# R302J.net
KiCad netlist of a schematic drawn in EAGLE
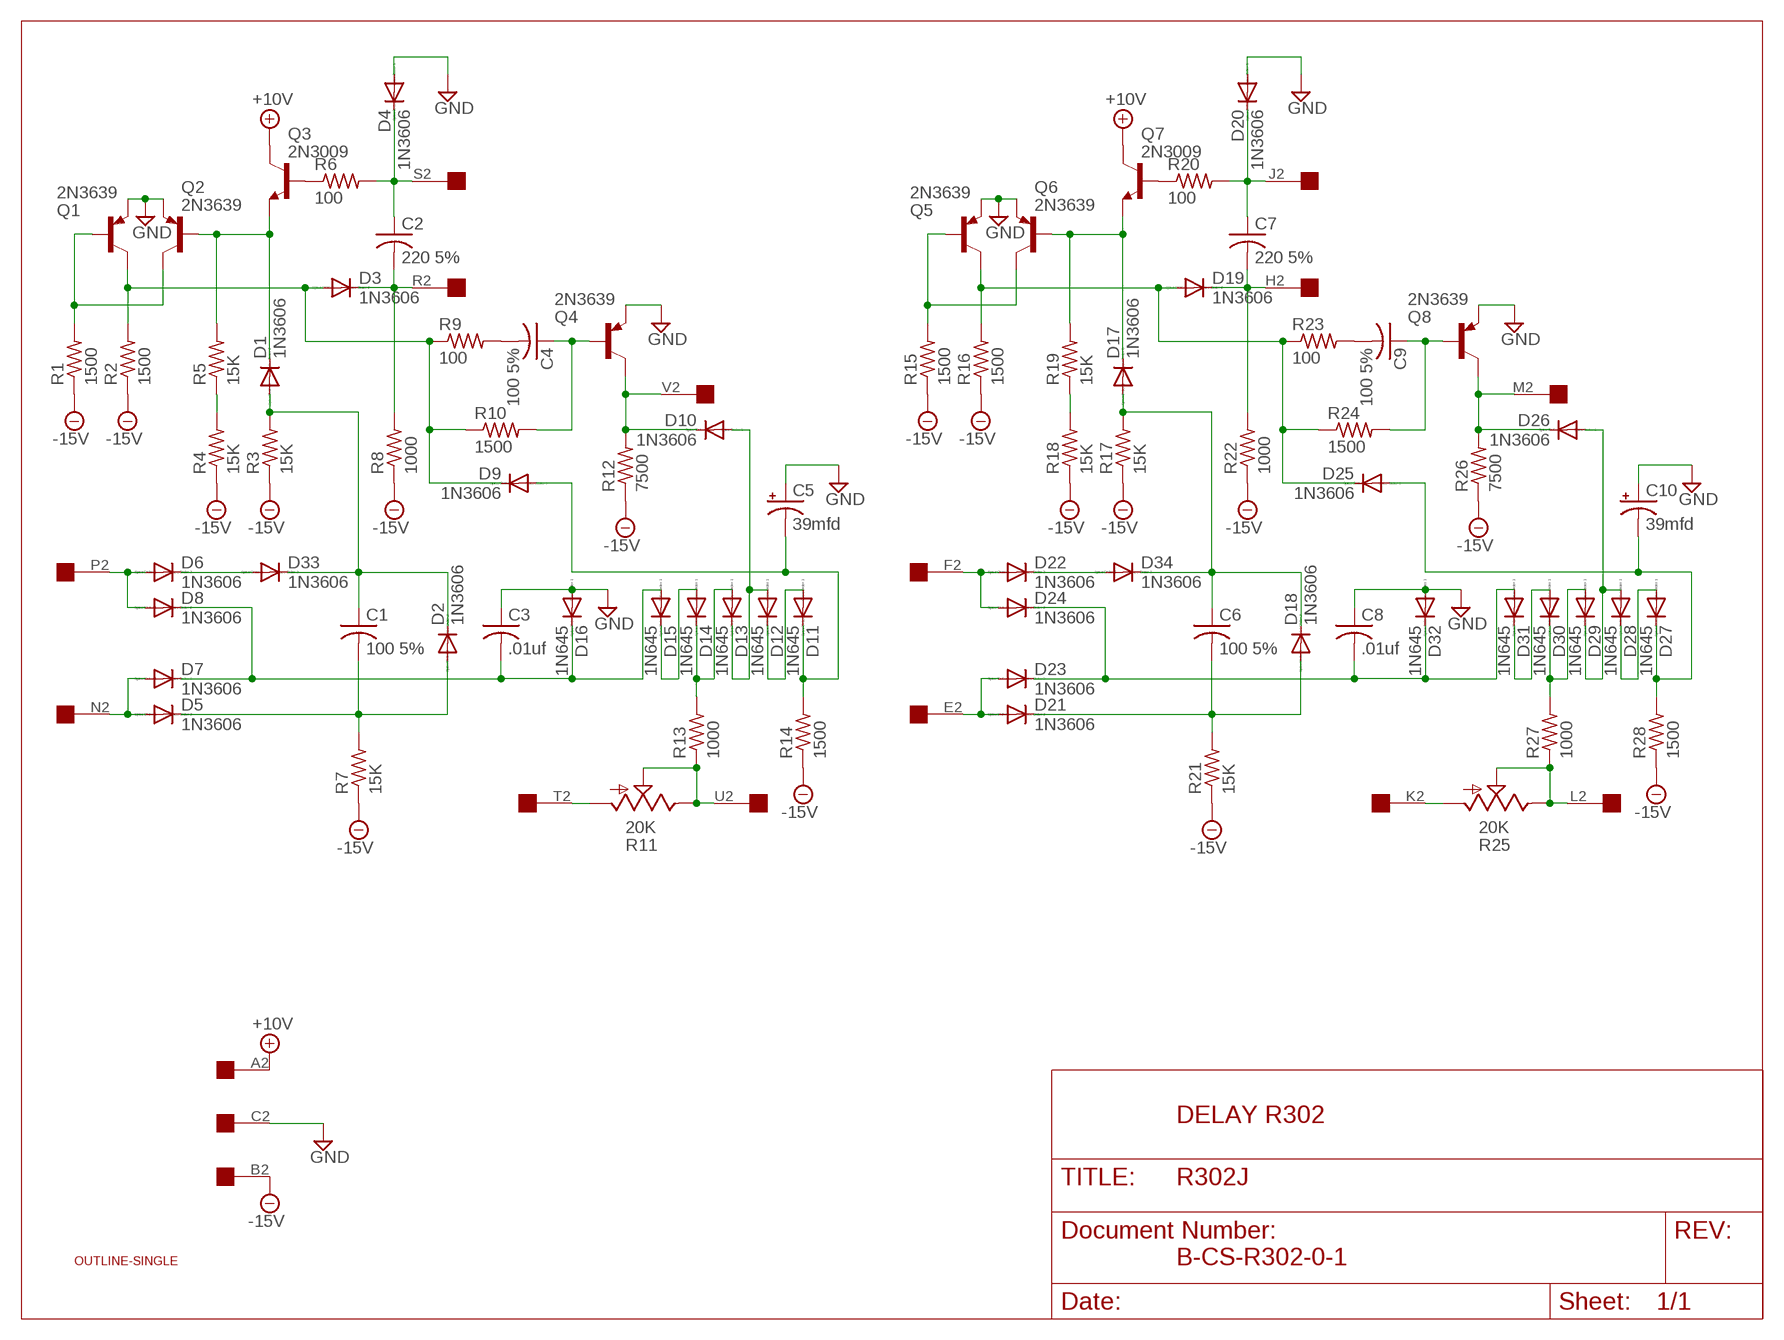
[diagram p0: schematic, sheet 1]

(export (version "E")
  (design (tool "Eeschema 10.0.6"))
  (components
    (comp (ref "C1")
      (value "100 5%")
      (footprint "eagle-import:C050-025X075")
      (libsource (lib "eagle-import") (part "C-US050-025X075"))
    )
    (comp (ref "C2")
      (value "220 5%")
      (footprint "eagle-import:C050-025X075")
      (libsource (lib "eagle-import") (part "C-US050-025X075"))
    )
    (comp (ref "C3")
      (value ".01uf")
      (footprint "eagle-import:C050-025X075")
      (libsource (lib "eagle-import") (part "C-US050-025X075"))
    )
    (comp (ref "C4")
      (value "100 5%")
      (footprint "eagle-import:C050-025X075")
      (libsource (lib "eagle-import") (part "C-US050-025X075"))
    )
    (comp (ref "C5")
      (value "39mfd")
      (footprint "eagle-import:E15-5")
      (libsource (lib "eagle-import") (part "CPOL-USE15-5AXIAL"))
    )
    (comp (ref "C6")
      (value "100 5%")
      (footprint "eagle-import:C050-025X075")
      (libsource (lib "eagle-import") (part "C-US050-025X075"))
    )
    (comp (ref "C7")
      (value "220 5%")
      (footprint "eagle-import:C050-025X075")
      (libsource (lib "eagle-import") (part "C-US050-025X075"))
    )
    (comp (ref "C8")
      (value ".01uf")
      (footprint "eagle-import:C050-025X075")
      (libsource (lib "eagle-import") (part "C-US050-025X075"))
    )
    (comp (ref "C9")
      (value "100 5%")
      (footprint "eagle-import:C050-025X075")
      (libsource (lib "eagle-import") (part "C-US050-025X075"))
    )
    (comp (ref "C10")
      (value "39mfd")
      (footprint "eagle-import:E15-5")
      (libsource (lib "eagle-import") (part "CPOL-USE15-5AXIAL"))
    )
    (comp (ref "D1")
      (value "1N3606")
      (footprint "eagle-import:DO35-10")
      (libsource (lib "eagle-import") (part "1N4148DO35-10"))
    )
    (comp (ref "D2")
      (value "1N3606")
      (footprint "eagle-import:DO35-10")
      (libsource (lib "eagle-import") (part "1N4148DO35-10"))
    )
    (comp (ref "D3")
      (value "1N3606")
      (footprint "eagle-import:DO35-10")
      (libsource (lib "eagle-import") (part "1N4148DO35-10"))
    )
    (comp (ref "D4")
      (value "1N3606")
      (footprint "eagle-import:DO35-10")
      (libsource (lib "eagle-import") (part "1N4148DO35-10"))
    )
    (comp (ref "D5")
      (value "1N3606")
      (footprint "eagle-import:DO35-10")
      (libsource (lib "eagle-import") (part "1N4148DO35-10"))
    )
    (comp (ref "D6")
      (value "1N3606")
      (footprint "eagle-import:DO35-10")
      (libsource (lib "eagle-import") (part "1N4148DO35-10"))
    )
    (comp (ref "D7")
      (value "1N3606")
      (footprint "eagle-import:DO35-10")
      (libsource (lib "eagle-import") (part "1N4148DO35-10"))
    )
    (comp (ref "D8")
      (value "1N3606")
      (footprint "eagle-import:DO35-10")
      (libsource (lib "eagle-import") (part "1N4148DO35-10"))
    )
    (comp (ref "D9")
      (value "1N3606")
      (footprint "eagle-import:DO35-10")
      (libsource (lib "eagle-import") (part "1N4148DO35-10"))
    )
    (comp (ref "D10")
      (value "1N3606")
      (footprint "eagle-import:DO35-10")
      (libsource (lib "eagle-import") (part "1N4148DO35-10"))
    )
    (comp (ref "D11")
      (value "1N645")
      (footprint "eagle-import:DO35-10")
      (libsource (lib "eagle-import") (part "1N4148DO35-10"))
    )
    (comp (ref "D12")
      (value "1N645")
      (footprint "eagle-import:DO35-10")
      (libsource (lib "eagle-import") (part "1N4148DO35-10"))
    )
    (comp (ref "D13")
      (value "1N645")
      (footprint "eagle-import:DO35-10")
      (libsource (lib "eagle-import") (part "1N4148DO35-10"))
    )
    (comp (ref "D14")
      (value "1N645")
      (footprint "eagle-import:DO35-10")
      (libsource (lib "eagle-import") (part "1N4148DO35-10"))
    )
    (comp (ref "D15")
      (value "1N645")
      (footprint "eagle-import:DO35-10")
      (libsource (lib "eagle-import") (part "1N4148DO35-10"))
    )
    (comp (ref "D16")
      (value "1N645")
      (footprint "eagle-import:DO35-10")
      (libsource (lib "eagle-import") (part "1N4148DO35-10"))
    )
    (comp (ref "D17")
      (value "1N3606")
      (footprint "eagle-import:DO35-10")
      (libsource (lib "eagle-import") (part "1N4148DO35-10"))
    )
    (comp (ref "D18")
      (value "1N3606")
      (footprint "eagle-import:DO35-10")
      (libsource (lib "eagle-import") (part "1N4148DO35-10"))
    )
    (comp (ref "D19")
      (value "1N3606")
      (footprint "eagle-import:DO35-10")
      (libsource (lib "eagle-import") (part "1N4148DO35-10"))
    )
    (comp (ref "D20")
      (value "1N3606")
      (footprint "eagle-import:DO35-10")
      (libsource (lib "eagle-import") (part "1N4148DO35-10"))
    )
    (comp (ref "D21")
      (value "1N3606")
      (footprint "eagle-import:DO35-10")
      (libsource (lib "eagle-import") (part "1N4148DO35-10"))
    )
    (comp (ref "D22")
      (value "1N3606")
      (footprint "eagle-import:DO35-10")
      (libsource (lib "eagle-import") (part "1N4148DO35-10"))
    )
    (comp (ref "D23")
      (value "1N3606")
      (footprint "eagle-import:DO35-10")
      (libsource (lib "eagle-import") (part "1N4148DO35-10"))
    )
    (comp (ref "D24")
      (value "1N3606")
      (footprint "eagle-import:DO35-10")
      (libsource (lib "eagle-import") (part "1N4148DO35-10"))
    )
    (comp (ref "D25")
      (value "1N3606")
      (footprint "eagle-import:DO35-10")
      (libsource (lib "eagle-import") (part "1N4148DO35-10"))
    )
    (comp (ref "D26")
      (value "1N3606")
      (footprint "eagle-import:DO35-10")
      (libsource (lib "eagle-import") (part "1N4148DO35-10"))
    )
    (comp (ref "D27")
      (value "1N645")
      (footprint "eagle-import:DO35-10")
      (libsource (lib "eagle-import") (part "1N4148DO35-10"))
    )
    (comp (ref "D28")
      (value "1N645")
      (footprint "eagle-import:DO35-10")
      (libsource (lib "eagle-import") (part "1N4148DO35-10"))
    )
    (comp (ref "D29")
      (value "1N645")
      (footprint "eagle-import:DO35-10")
      (libsource (lib "eagle-import") (part "1N4148DO35-10"))
    )
    (comp (ref "D30")
      (value "1N645")
      (footprint "eagle-import:DO35-10")
      (libsource (lib "eagle-import") (part "1N4148DO35-10"))
    )
    (comp (ref "D31")
      (value "1N645")
      (footprint "eagle-import:DO35-10")
      (libsource (lib "eagle-import") (part "1N4148DO35-10"))
    )
    (comp (ref "D32")
      (value "1N645")
      (footprint "eagle-import:DO35-10")
      (libsource (lib "eagle-import") (part "1N4148DO35-10"))
    )
    (comp (ref "D33")
      (value "1N3606")
      (footprint "eagle-import:DO35-10")
      (libsource (lib "eagle-import") (part "1N4148DO35-10"))
    )
    (comp (ref "D34")
      (value "1N3606")
      (footprint "eagle-import:DO35-10")
      (libsource (lib "eagle-import") (part "1N4148DO35-10"))
    )
    (comp (ref "Q1")
      (value "2N3639")
      (footprint "eagle-import:TO39")
      (libsource (lib "eagle-import") (part "2N3637"))
    )
    (comp (ref "Q2")
      (value "2N3639")
      (footprint "eagle-import:TO39")
      (libsource (lib "eagle-import") (part "2N3637"))
    )
    (comp (ref "Q3")
      (value "2N3009")
      (footprint "eagle-import:TO39")
      (libsource (lib "eagle-import") (part "-NPN-TO39-EBC2N3019"))
    )
    (comp (ref "Q4")
      (value "2N3639")
      (footprint "eagle-import:TO39")
      (libsource (lib "eagle-import") (part "2N3637"))
    )
    (comp (ref "Q5")
      (value "2N3639")
      (footprint "eagle-import:TO39")
      (libsource (lib "eagle-import") (part "2N3637"))
    )
    (comp (ref "Q6")
      (value "2N3639")
      (footprint "eagle-import:TO39")
      (libsource (lib "eagle-import") (part "2N3637"))
    )
    (comp (ref "Q7")
      (value "2N3009")
      (footprint "eagle-import:TO39")
      (libsource (lib "eagle-import") (part "-NPN-TO39-EBC2N3019"))
    )
    (comp (ref "Q8")
      (value "2N3639")
      (footprint "eagle-import:TO39")
      (libsource (lib "eagle-import") (part "2N3637"))
    )
    (comp (ref "R1")
      (value "1500")
      (footprint "eagle-import:0207_10")
      (libsource (lib "eagle-import") (part "R-US_0207/10"))
    )
    (comp (ref "R2")
      (value "1500")
      (footprint "eagle-import:0207_10")
      (libsource (lib "eagle-import") (part "R-US_0207/10"))
    )
    (comp (ref "R3")
      (value "15K")
      (footprint "eagle-import:0207_10")
      (libsource (lib "eagle-import") (part "R-US_0207/10"))
    )
    (comp (ref "R4")
      (value "15K")
      (footprint "eagle-import:0207_10")
      (libsource (lib "eagle-import") (part "R-US_0207/10"))
    )
    (comp (ref "R5")
      (value "15K")
      (footprint "eagle-import:0207_10")
      (libsource (lib "eagle-import") (part "R-US_0207/10"))
    )
    (comp (ref "R6")
      (value "100")
      (footprint "eagle-import:0207_10")
      (libsource (lib "eagle-import") (part "R-US_0207/10"))
    )
    (comp (ref "R7")
      (value "15K")
      (footprint "eagle-import:0207_10")
      (libsource (lib "eagle-import") (part "R-US_0207/10"))
    )
    (comp (ref "R8")
      (value "1000")
      (footprint "eagle-import:0207_10")
      (libsource (lib "eagle-import") (part "R-US_0207/10"))
    )
    (comp (ref "R9")
      (value "100")
      (footprint "eagle-import:0207_10")
      (libsource (lib "eagle-import") (part "R-US_0207/10"))
    )
    (comp (ref "R10")
      (value "1500")
      (footprint "eagle-import:0207_10")
      (libsource (lib "eagle-import") (part "R-US_0207/10"))
    )
    (comp (ref "R11")
      (value "20K")
      (footprint "eagle-import:SP19L")
      (libsource (lib "eagle-import") (part "TRIM_US-S43P"))
    )
    (comp (ref "R12")
      (value "7500")
      (footprint "eagle-import:0207_10")
      (libsource (lib "eagle-import") (part "R-US_0207/10"))
    )
    (comp (ref "R13")
      (value "1000")
      (footprint "eagle-import:0207_10")
      (libsource (lib "eagle-import") (part "R-US_0207/10"))
    )
    (comp (ref "R14")
      (value "1500")
      (footprint "eagle-import:0207_10")
      (libsource (lib "eagle-import") (part "R-US_0207/10"))
    )
    (comp (ref "R15")
      (value "1500")
      (footprint "eagle-import:0207_10")
      (libsource (lib "eagle-import") (part "R-US_0207/10"))
    )
    (comp (ref "R16")
      (value "1500")
      (footprint "eagle-import:0207_10")
      (libsource (lib "eagle-import") (part "R-US_0207/10"))
    )
    (comp (ref "R17")
      (value "15K")
      (footprint "eagle-import:0207_10")
      (libsource (lib "eagle-import") (part "R-US_0207/10"))
    )
    (comp (ref "R18")
      (value "15K")
      (footprint "eagle-import:0207_10")
      (libsource (lib "eagle-import") (part "R-US_0207/10"))
    )
    (comp (ref "R19")
      (value "15K")
      (footprint "eagle-import:0207_10")
      (libsource (lib "eagle-import") (part "R-US_0207/10"))
    )
    (comp (ref "R20")
      (value "100")
      (footprint "eagle-import:0207_10")
      (libsource (lib "eagle-import") (part "R-US_0207/10"))
    )
    (comp (ref "R21")
      (value "15K")
      (footprint "eagle-import:0207_10")
      (libsource (lib "eagle-import") (part "R-US_0207/10"))
    )
    (comp (ref "R22")
      (value "1000")
      (footprint "eagle-import:0207_10")
      (libsource (lib "eagle-import") (part "R-US_0207/10"))
    )
    (comp (ref "R23")
      (value "100")
      (footprint "eagle-import:0207_10")
      (libsource (lib "eagle-import") (part "R-US_0207/10"))
    )
    (comp (ref "R24")
      (value "1500")
      (footprint "eagle-import:0207_10")
      (libsource (lib "eagle-import") (part "R-US_0207/10"))
    )
    (comp (ref "R25")
      (value "20K")
      (footprint "eagle-import:SP19L")
      (libsource (lib "eagle-import") (part "TRIM_US-S43P"))
    )
    (comp (ref "R26")
      (value "7500")
      (footprint "eagle-import:0207_10")
      (libsource (lib "eagle-import") (part "R-US_0207/10"))
    )
    (comp (ref "R27")
      (value "1000")
      (footprint "eagle-import:0207_10")
      (libsource (lib "eagle-import") (part "R-US_0207/10"))
    )
    (comp (ref "R28")
      (value "1500")
      (footprint "eagle-import:0207_10")
      (libsource (lib "eagle-import") (part "R-US_0207/10"))
    )
    (comp (ref "U$1")
      (value "OUTLINE-SINGLE")
      (footprint "eagle-import:SINGLE")
      (libsource (lib "eagle-import") (part "OUTLINE-SINGLE"))
    )
    (comp (ref "U$2")
      (value "EDGE-1")
      (footprint "eagle-import:EDGE-CON1")
      (libsource (lib "eagle-import") (part "EDGE-1"))
    )
  )
  (nets
    (net (code "1") (name "+10V") (class "Default")
      (node (ref "Q3") (pin "3") (pinfunction "C_3") (pintype "passive"))
      (node (ref "Q7") (pin "3") (pinfunction "C_3") (pintype "passive"))
      (node (ref "U$2") (pin "A2") (pinfunction "1_A2") (pintype "bidirectional"))
    )
    (net (code "2") (name "-15V") (class "Default")
      (node (ref "R1") (pin "1") (pinfunction "1_1") (pintype "passive"))
      (node (ref "R12") (pin "1") (pinfunction "1_1") (pintype "passive"))
      (node (ref "R14") (pin "1") (pinfunction "1_1") (pintype "passive"))
      (node (ref "R15") (pin "1") (pinfunction "1_1") (pintype "passive"))
      (node (ref "R16") (pin "1") (pinfunction "1_1") (pintype "passive"))
      (node (ref "R17") (pin "1") (pinfunction "1_1") (pintype "passive"))
      (node (ref "R18") (pin "1") (pinfunction "1_1") (pintype "passive"))
      (node (ref "R2") (pin "1") (pinfunction "1_1") (pintype "passive"))
      (node (ref "R21") (pin "1") (pinfunction "1_1") (pintype "passive"))
      (node (ref "R22") (pin "1") (pinfunction "1_1") (pintype "passive"))
      (node (ref "R26") (pin "1") (pinfunction "1_1") (pintype "passive"))
      (node (ref "R28") (pin "1") (pinfunction "1_1") (pintype "passive"))
      (node (ref "R3") (pin "1") (pinfunction "1_1") (pintype "passive"))
      (node (ref "R4") (pin "1") (pinfunction "1_1") (pintype "passive"))
      (node (ref "R7") (pin "1") (pinfunction "1_1") (pintype "passive"))
      (node (ref "R8") (pin "1") (pinfunction "1_1") (pintype "passive"))
      (node (ref "U$2") (pin "B2") (pinfunction "1_B2") (pintype "bidirectional"))
    )
    (net (code "3") (name "GND") (class "Default")
      (node (ref "C10") (pin "+") (pinfunction "+_+") (pintype "passive"))
      (node (ref "C3") (pin "1") (pinfunction "1_1") (pintype "passive"))
      (node (ref "C5") (pin "+") (pinfunction "+_+") (pintype "passive"))
      (node (ref "C8") (pin "1") (pinfunction "1_1") (pintype "passive"))
      (node (ref "D16") (pin "A") (pinfunction "A_A") (pintype "passive"))
      (node (ref "D20") (pin "A") (pinfunction "A_A") (pintype "passive"))
      (node (ref "D32") (pin "A") (pinfunction "A_A") (pintype "passive"))
      (node (ref "D4") (pin "A") (pinfunction "A_A") (pintype "passive"))
      (node (ref "Q1") (pin "1") (pinfunction "E_1") (pintype "passive"))
      (node (ref "Q2") (pin "1") (pinfunction "E_1") (pintype "passive"))
      (node (ref "Q4") (pin "1") (pinfunction "E_1") (pintype "passive"))
      (node (ref "Q5") (pin "1") (pinfunction "E_1") (pintype "passive"))
      (node (ref "Q6") (pin "1") (pinfunction "E_1") (pintype "passive"))
      (node (ref "Q8") (pin "1") (pinfunction "E_1") (pintype "passive"))
      (node (ref "U$2") (pin "C2") (pinfunction "1_C2") (pintype "bidirectional"))
    )
    (net (code "4") (name "Net-(C1-Pad1)") (class "Default")
      (node (ref "C1") (pin "1") (pinfunction "1_1") (pintype "passive"))
      (node (ref "D1") (pin "A") (pinfunction "A_A") (pintype "passive"))
      (node (ref "D2") (pin "C") (pinfunction "C_C") (pintype "passive"))
      (node (ref "D33") (pin "C") (pinfunction "C_C") (pintype "passive"))
      (node (ref "R3") (pin "2") (pinfunction "2_2") (pintype "passive"))
    )
    (net (code "5") (name "Net-(C1-Pad2)") (class "Default")
      (node (ref "C1") (pin "2") (pinfunction "2_2") (pintype "passive"))
      (node (ref "D2") (pin "A") (pinfunction "A_A") (pintype "passive"))
      (node (ref "D5") (pin "C") (pinfunction "C_C") (pintype "passive"))
      (node (ref "R7") (pin "2") (pinfunction "2_2") (pintype "passive"))
    )
    (net (code "6") (name "Net-(C3-Pad2)") (class "Default")
      (node (ref "C3") (pin "2") (pinfunction "2_2") (pintype "passive"))
      (node (ref "D15") (pin "A") (pinfunction "A_A") (pintype "passive"))
      (node (ref "D16") (pin "C") (pinfunction "C_C") (pintype "passive"))
      (node (ref "D7") (pin "C") (pinfunction "C_C") (pintype "passive"))
      (node (ref "D8") (pin "C") (pinfunction "C_C") (pintype "passive"))
    )
    (net (code "7") (name "Net-(C4-Pad2)") (class "Default")
      (node (ref "C4") (pin "2") (pinfunction "2_2") (pintype "passive"))
      (node (ref "R9") (pin "2") (pinfunction "2_2") (pintype "passive"))
    )
    (net (code "8") (name "Net-(C5-Pad-)") (class "Default")
      (node (ref "C5") (pin "-") (pinfunction "-_-") (pintype "passive"))
      (node (ref "D11") (pin "C") (pinfunction "C_C") (pintype "passive"))
      (node (ref "D9") (pin "A") (pinfunction "A_A") (pintype "passive"))
      (node (ref "R14") (pin "2") (pinfunction "2_2") (pintype "passive"))
    )
    (net (code "9") (name "Net-(C6-Pad1)") (class "Default")
      (node (ref "C6") (pin "1") (pinfunction "1_1") (pintype "passive"))
      (node (ref "D17") (pin "A") (pinfunction "A_A") (pintype "passive"))
      (node (ref "D18") (pin "C") (pinfunction "C_C") (pintype "passive"))
      (node (ref "D34") (pin "C") (pinfunction "C_C") (pintype "passive"))
      (node (ref "R17") (pin "2") (pinfunction "2_2") (pintype "passive"))
    )
    (net (code "10") (name "Net-(C6-Pad2)") (class "Default")
      (node (ref "C6") (pin "2") (pinfunction "2_2") (pintype "passive"))
      (node (ref "D18") (pin "A") (pinfunction "A_A") (pintype "passive"))
      (node (ref "D21") (pin "C") (pinfunction "C_C") (pintype "passive"))
      (node (ref "R21") (pin "2") (pinfunction "2_2") (pintype "passive"))
    )
    (net (code "11") (name "Net-(C8-Pad2)") (class "Default")
      (node (ref "C8") (pin "2") (pinfunction "2_2") (pintype "passive"))
      (node (ref "D23") (pin "C") (pinfunction "C_C") (pintype "passive"))
      (node (ref "D24") (pin "C") (pinfunction "C_C") (pintype "passive"))
      (node (ref "D31") (pin "A") (pinfunction "A_A") (pintype "passive"))
      (node (ref "D32") (pin "C") (pinfunction "C_C") (pintype "passive"))
    )
    (net (code "12") (name "Net-(C9-Pad2)") (class "Default")
      (node (ref "C9") (pin "2") (pinfunction "2_2") (pintype "passive"))
      (node (ref "R23") (pin "2") (pinfunction "2_2") (pintype "passive"))
    )
    (net (code "13") (name "Net-(C10-Pad-)") (class "Default")
      (node (ref "C10") (pin "-") (pinfunction "-_-") (pintype "passive"))
      (node (ref "D25") (pin "A") (pinfunction "A_A") (pintype "passive"))
      (node (ref "D27") (pin "C") (pinfunction "C_C") (pintype "passive"))
      (node (ref "R28") (pin "2") (pinfunction "2_2") (pintype "passive"))
    )
    (net (code "14") (name "Net-(D10-PadA)") (class "Default")
      (node (ref "D10") (pin "A") (pinfunction "A_A") (pintype "passive"))
      (node (ref "D12") (pin "A") (pinfunction "A_A") (pintype "passive"))
      (node (ref "D13") (pin "C") (pinfunction "C_C") (pintype "passive"))
    )
    (net (code "15") (name "Net-(D11-PadA)") (class "Default")
      (node (ref "D11") (pin "A") (pinfunction "A_A") (pintype "passive"))
      (node (ref "D12") (pin "C") (pinfunction "C_C") (pintype "passive"))
    )
    (net (code "16") (name "Net-(D13-PadA)") (class "Default")
      (node (ref "D13") (pin "A") (pinfunction "A_A") (pintype "passive"))
      (node (ref "D14") (pin "C") (pinfunction "C_C") (pintype "passive"))
      (node (ref "R13") (pin "2") (pinfunction "2_2") (pintype "passive"))
    )
    (net (code "17") (name "Net-(D14-PadA)") (class "Default")
      (node (ref "D14") (pin "A") (pinfunction "A_A") (pintype "passive"))
      (node (ref "D15") (pin "C") (pinfunction "C_C") (pintype "passive"))
    )
    (net (code "18") (name "Net-(D22-PadC)") (class "Default")
      (node (ref "D22") (pin "C") (pinfunction "C_C") (pintype "passive"))
      (node (ref "D34") (pin "A") (pinfunction "A_A") (pintype "passive"))
    )
    (net (code "19") (name "Net-(D26-PadA)") (class "Default")
      (node (ref "D26") (pin "A") (pinfunction "A_A") (pintype "passive"))
      (node (ref "D28") (pin "A") (pinfunction "A_A") (pintype "passive"))
      (node (ref "D29") (pin "C") (pinfunction "C_C") (pintype "passive"))
    )
    (net (code "20") (name "Net-(D27-PadA)") (class "Default")
      (node (ref "D27") (pin "A") (pinfunction "A_A") (pintype "passive"))
      (node (ref "D28") (pin "C") (pinfunction "C_C") (pintype "passive"))
    )
    (net (code "21") (name "Net-(D29-PadA)") (class "Default")
      (node (ref "D29") (pin "A") (pinfunction "A_A") (pintype "passive"))
      (node (ref "D30") (pin "C") (pinfunction "C_C") (pintype "passive"))
      (node (ref "R27") (pin "2") (pinfunction "2_2") (pintype "passive"))
    )
    (net (code "22") (name "Net-(D30-PadA)") (class "Default")
      (node (ref "D30") (pin "A") (pinfunction "A_A") (pintype "passive"))
      (node (ref "D31") (pin "C") (pinfunction "C_C") (pintype "passive"))
    )
    (net (code "23") (name "Net-(D33-PadA)") (class "Default")
      (node (ref "D33") (pin "A") (pinfunction "A_A") (pintype "passive"))
      (node (ref "D6") (pin "C") (pinfunction "C_C") (pintype "passive"))
    )
    (net (code "24") (name "Net-(Q1-B)") (class "Default")
      (node (ref "Q1") (pin "2") (pinfunction "B_2") (pintype "passive"))
      (node (ref "Q2") (pin "3") (pinfunction "C_3") (pintype "passive"))
      (node (ref "R1") (pin "2") (pinfunction "2_2") (pintype "passive"))
    )
    (net (code "25") (name "Net-(Q1-C)") (class "Default")
      (node (ref "D3") (pin "A") (pinfunction "A_A") (pintype "passive"))
      (node (ref "D9") (pin "C") (pinfunction "C_C") (pintype "passive"))
      (node (ref "Q1") (pin "3") (pinfunction "C_3") (pintype "passive"))
      (node (ref "R10") (pin "1") (pinfunction "1_1") (pintype "passive"))
      (node (ref "R2") (pin "2") (pinfunction "2_2") (pintype "passive"))
      (node (ref "R9") (pin "1") (pinfunction "1_1") (pintype "passive"))
    )
    (net (code "26") (name "Net-(Q2-B)") (class "Default")
      (node (ref "D1") (pin "C") (pinfunction "C_C") (pintype "passive"))
      (node (ref "Q2") (pin "2") (pinfunction "B_2") (pintype "passive"))
      (node (ref "Q3") (pin "1") (pinfunction "E_1") (pintype "passive"))
      (node (ref "R5") (pin "2") (pinfunction "2_2") (pintype "passive"))
    )
    (net (code "27") (name "Net-(Q3-B)") (class "Default")
      (node (ref "Q3") (pin "2") (pinfunction "B_2") (pintype "passive"))
      (node (ref "R6") (pin "1") (pinfunction "1_1") (pintype "passive"))
    )
    (net (code "28") (name "Net-(Q4-B)") (class "Default")
      (node (ref "C4") (pin "1") (pinfunction "1_1") (pintype "passive"))
      (node (ref "Q4") (pin "2") (pinfunction "B_2") (pintype "passive"))
      (node (ref "R10") (pin "2") (pinfunction "2_2") (pintype "passive"))
    )
    (net (code "29") (name "Net-(Q4-C)") (class "Default")
      (node (ref "D10") (pin "C") (pinfunction "C_C") (pintype "passive"))
      (node (ref "Q4") (pin "3") (pinfunction "C_3") (pintype "passive"))
      (node (ref "R12") (pin "2") (pinfunction "2_2") (pintype "passive"))
      (node (ref "U$2") (pin "V2") (pinfunction "1_V2") (pintype "bidirectional"))
    )
    (net (code "30") (name "Net-(Q5-B)") (class "Default")
      (node (ref "Q5") (pin "2") (pinfunction "B_2") (pintype "passive"))
      (node (ref "Q6") (pin "3") (pinfunction "C_3") (pintype "passive"))
      (node (ref "R15") (pin "2") (pinfunction "2_2") (pintype "passive"))
    )
    (net (code "31") (name "Net-(Q5-C)") (class "Default")
      (node (ref "D19") (pin "A") (pinfunction "A_A") (pintype "passive"))
      (node (ref "D25") (pin "C") (pinfunction "C_C") (pintype "passive"))
      (node (ref "Q5") (pin "3") (pinfunction "C_3") (pintype "passive"))
      (node (ref "R16") (pin "2") (pinfunction "2_2") (pintype "passive"))
      (node (ref "R23") (pin "1") (pinfunction "1_1") (pintype "passive"))
      (node (ref "R24") (pin "1") (pinfunction "1_1") (pintype "passive"))
    )
    (net (code "32") (name "Net-(Q6-B)") (class "Default")
      (node (ref "D17") (pin "C") (pinfunction "C_C") (pintype "passive"))
      (node (ref "Q6") (pin "2") (pinfunction "B_2") (pintype "passive"))
      (node (ref "Q7") (pin "1") (pinfunction "E_1") (pintype "passive"))
      (node (ref "R19") (pin "2") (pinfunction "2_2") (pintype "passive"))
    )
    (net (code "33") (name "Net-(Q7-B)") (class "Default")
      (node (ref "Q7") (pin "2") (pinfunction "B_2") (pintype "passive"))
      (node (ref "R20") (pin "1") (pinfunction "1_1") (pintype "passive"))
    )
    (net (code "34") (name "Net-(Q8-B)") (class "Default")
      (node (ref "C9") (pin "1") (pinfunction "1_1") (pintype "passive"))
      (node (ref "Q8") (pin "2") (pinfunction "B_2") (pintype "passive"))
      (node (ref "R24") (pin "2") (pinfunction "2_2") (pintype "passive"))
    )
    (net (code "35") (name "Net-(Q8-C)") (class "Default")
      (node (ref "D26") (pin "C") (pinfunction "C_C") (pintype "passive"))
      (node (ref "Q8") (pin "3") (pinfunction "C_3") (pintype "passive"))
      (node (ref "R26") (pin "2") (pinfunction "2_2") (pintype "passive"))
      (node (ref "U$2") (pin "M2") (pinfunction "1_M2") (pintype "bidirectional"))
    )
    (net (code "36") (name "Net-(R4-Pad2)") (class "Default")
      (node (ref "R4") (pin "2") (pinfunction "2_2") (pintype "passive"))
      (node (ref "R5") (pin "1") (pinfunction "1_1") (pintype "passive"))
    )
    (net (code "37") (name "Net-(R18-Pad2)") (class "Default")
      (node (ref "R18") (pin "2") (pinfunction "2_2") (pintype "passive"))
      (node (ref "R19") (pin "1") (pinfunction "1_1") (pintype "passive"))
    )
    (net (code "38") (name "Net-(U$2E-1)") (class "Default")
      (node (ref "D21") (pin "A") (pinfunction "A_A") (pintype "passive"))
      (node (ref "D23") (pin "A") (pinfunction "A_A") (pintype "passive"))
      (node (ref "U$2") (pin "E2") (pinfunction "1_E2") (pintype "bidirectional"))
    )
    (net (code "39") (name "Net-(U$2F-1)") (class "Default")
      (node (ref "D22") (pin "A") (pinfunction "A_A") (pintype "passive"))
      (node (ref "D24") (pin "A") (pinfunction "A_A") (pintype "passive"))
      (node (ref "U$2") (pin "F2") (pinfunction "1_F2") (pintype "bidirectional"))
    )
    (net (code "40") (name "Net-(U$2G-1)") (class "Default")
      (node (ref "C7") (pin "2") (pinfunction "2_2") (pintype "passive"))
      (node (ref "D19") (pin "C") (pinfunction "C_C") (pintype "passive"))
      (node (ref "R22") (pin "2") (pinfunction "2_2") (pintype "passive"))
      (node (ref "U$2") (pin "H2") (pinfunction "1_H2") (pintype "bidirectional"))
    )
    (net (code "41") (name "Net-(U$2H-1)") (class "Default")
      (node (ref "C7") (pin "1") (pinfunction "1_1") (pintype "passive"))
      (node (ref "D20") (pin "C") (pinfunction "C_C") (pintype "passive"))
      (node (ref "R20") (pin "2") (pinfunction "2_2") (pintype "passive"))
      (node (ref "U$2") (pin "J2") (pinfunction "1_J2") (pintype "bidirectional"))
    )
    (net (code "42") (name "Net-(U$2I-1)") (class "Default")
      (node (ref "R25") (pin "A") (pinfunction "A_A") (pintype "passive"))
      (node (ref "U$2") (pin "K2") (pinfunction "1_K2") (pintype "bidirectional"))
    )
    (net (code "43") (name "Net-(U$2J-1)") (class "Default")
      (node (ref "R25") (pin "E") (pinfunction "E_E") (pintype "passive"))
      (node (ref "R25") (pin "S") (pinfunction "S_S") (pintype "passive"))
      (node (ref "R27") (pin "1") (pinfunction "1_1") (pintype "passive"))
      (node (ref "U$2") (pin "L2") (pinfunction "1_L2") (pintype "bidirectional"))
    )
    (net (code "44") (name "Net-(U$2L-1)") (class "Default")
      (node (ref "D5") (pin "A") (pinfunction "A_A") (pintype "passive"))
      (node (ref "D7") (pin "A") (pinfunction "A_A") (pintype "passive"))
      (node (ref "U$2") (pin "N2") (pinfunction "1_N2") (pintype "bidirectional"))
    )
    (net (code "45") (name "Net-(U$2M-1)") (class "Default")
      (node (ref "D6") (pin "A") (pinfunction "A_A") (pintype "passive"))
      (node (ref "D8") (pin "A") (pinfunction "A_A") (pintype "passive"))
      (node (ref "U$2") (pin "P2") (pinfunction "1_P2") (pintype "bidirectional"))
    )
    (net (code "46") (name "Net-(U$2N-1)") (class "Default")
      (node (ref "C2") (pin "2") (pinfunction "2_2") (pintype "passive"))
      (node (ref "D3") (pin "C") (pinfunction "C_C") (pintype "passive"))
      (node (ref "R8") (pin "2") (pinfunction "2_2") (pintype "passive"))
      (node (ref "U$2") (pin "R2") (pinfunction "1_R2") (pintype "bidirectional"))
    )
    (net (code "47") (name "Net-(U$2O-1)") (class "Default")
      (node (ref "C2") (pin "1") (pinfunction "1_1") (pintype "passive"))
      (node (ref "D4") (pin "C") (pinfunction "C_C") (pintype "passive"))
      (node (ref "R6") (pin "2") (pinfunction "2_2") (pintype "passive"))
      (node (ref "U$2") (pin "S2") (pinfunction "1_S2") (pintype "bidirectional"))
    )
    (net (code "48") (name "Net-(U$2P-1)") (class "Default")
      (node (ref "R11") (pin "A") (pinfunction "A_A") (pintype "passive"))
      (node (ref "U$2") (pin "T2") (pinfunction "1_T2") (pintype "bidirectional"))
    )
    (net (code "49") (name "Net-(U$2Q-1)") (class "Default")
      (node (ref "R11") (pin "E") (pinfunction "E_E") (pintype "passive"))
      (node (ref "R11") (pin "S") (pinfunction "S_S") (pintype "passive"))
      (node (ref "R13") (pin "1") (pinfunction "1_1") (pintype "passive"))
      (node (ref "U$2") (pin "U2") (pinfunction "1_U2") (pintype "bidirectional"))
    )
  )
)
